# 07-PowerManagement.net
KiCad netlist of a schematic drawn in Altium Designer
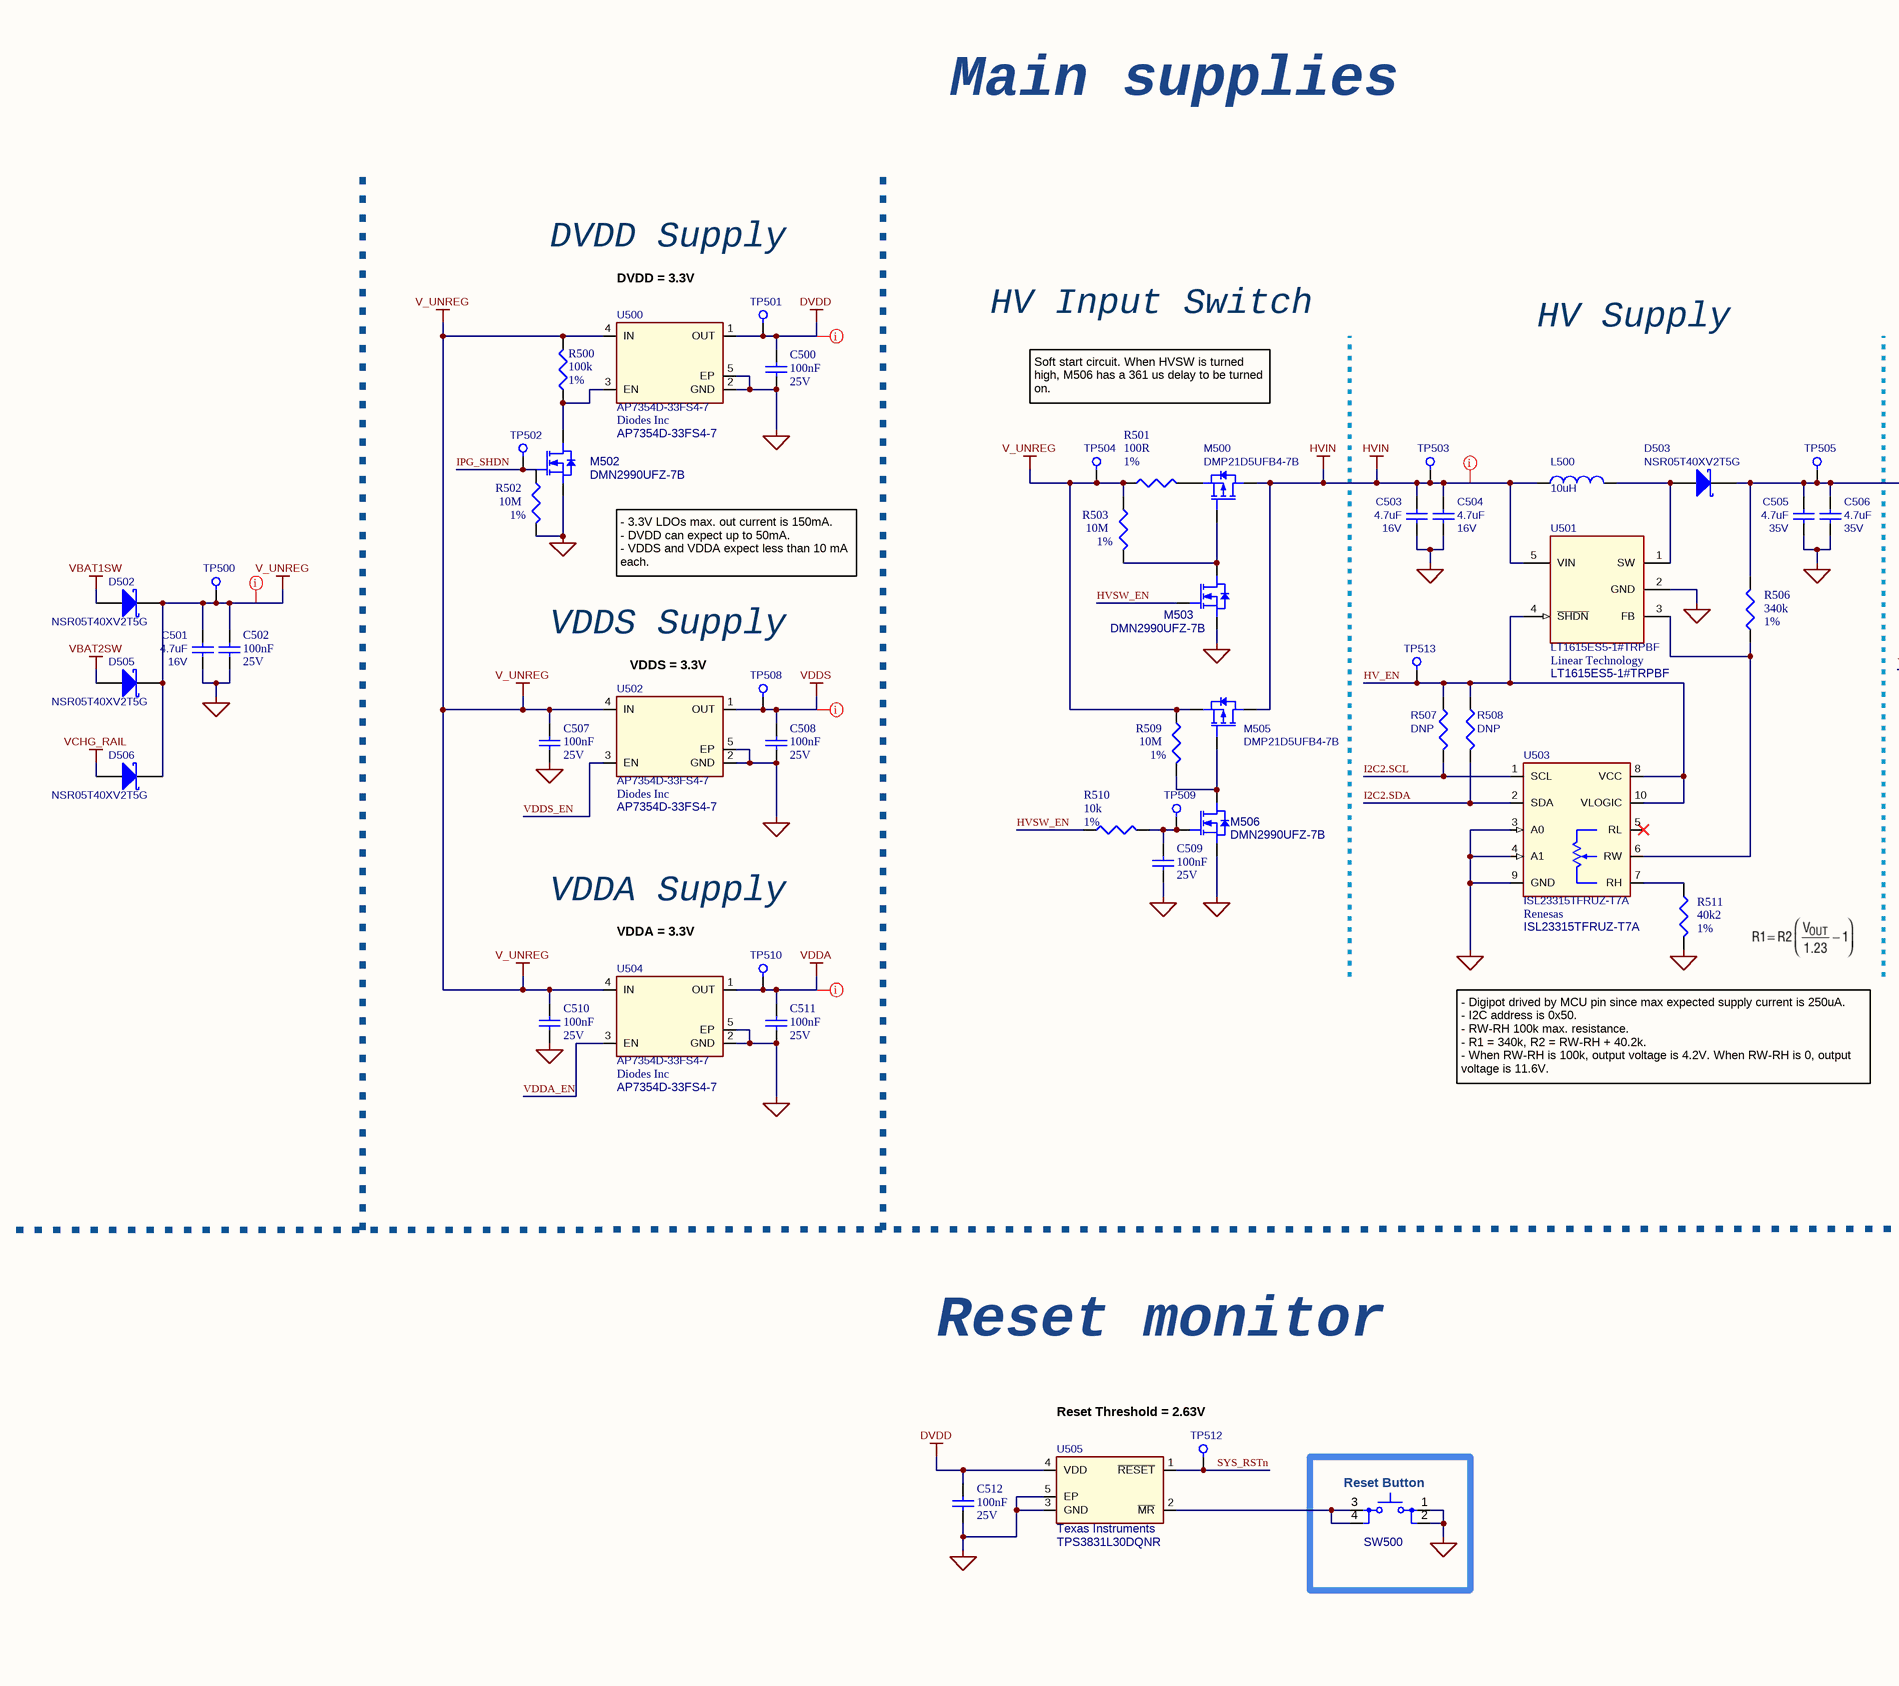
[diagram p0: 07-PowerManagement.SchDoc, left]
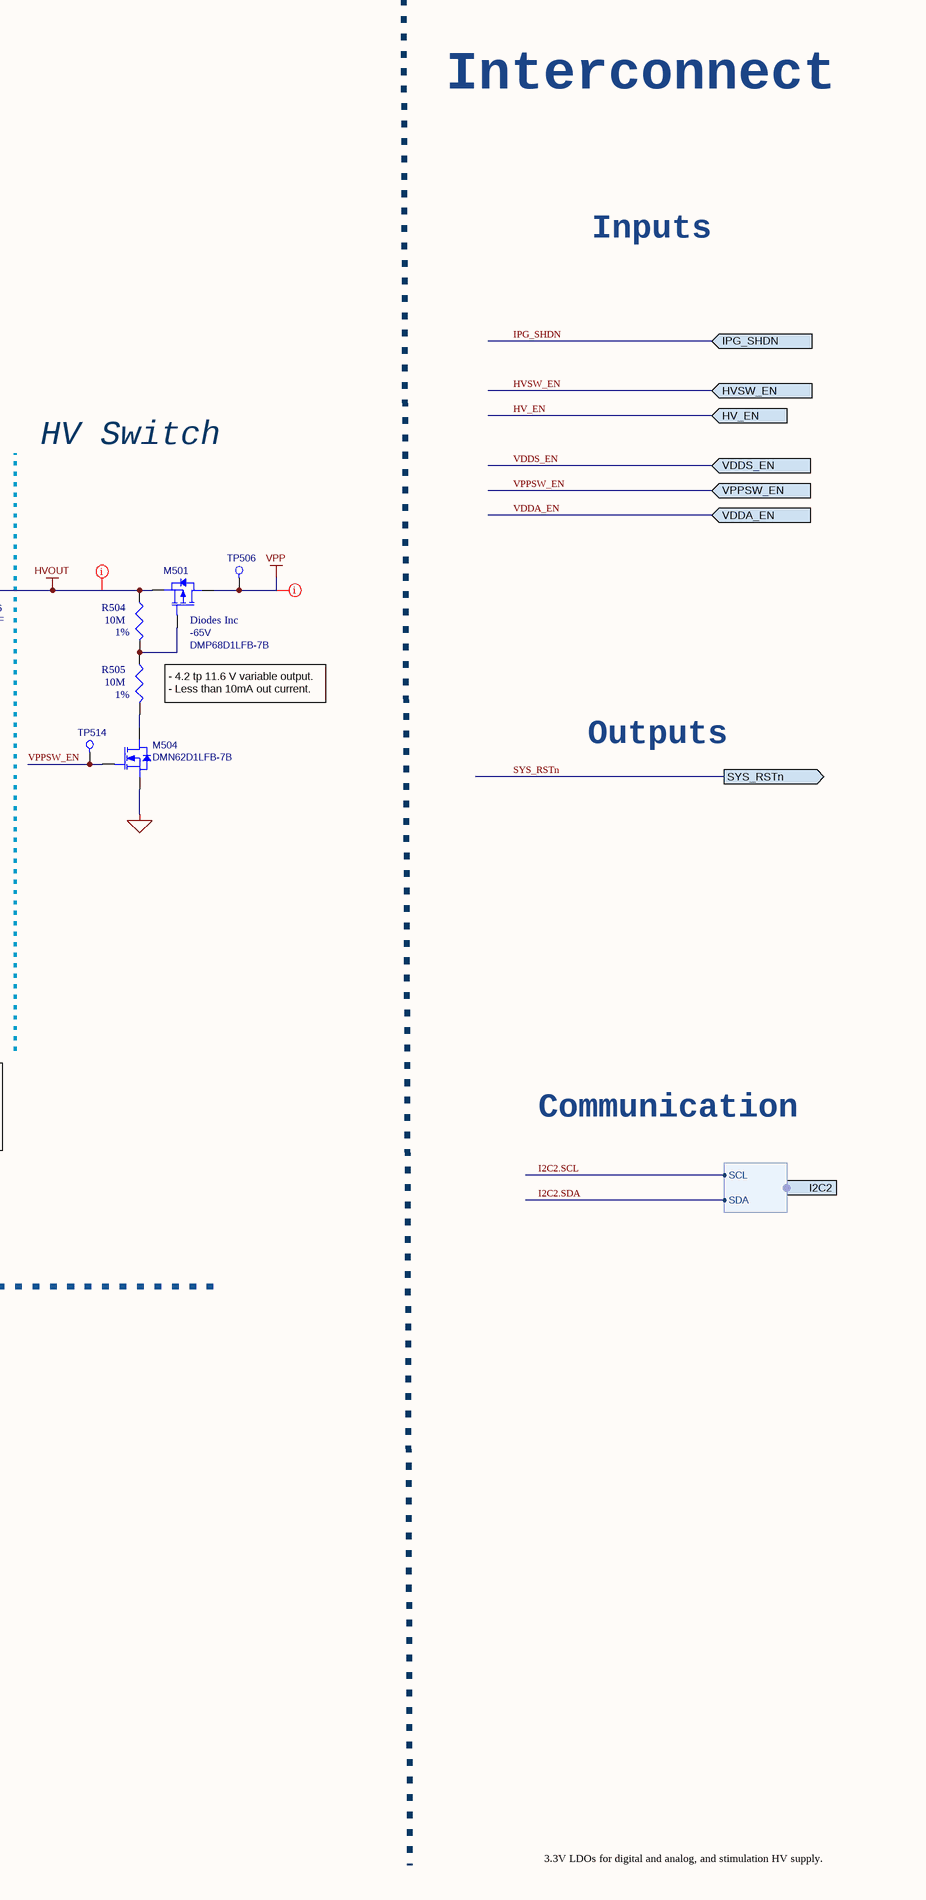
[diagram p1: 07-PowerManagement.SchDoc, right]

(export (version "E")
  (design (tool "Eeschema 10.0.6"))
  (components
    (comp (ref "C500")
      (value "100nF")
      (footprint "C0201_C")
      (fields
        (field (name "MANUFACTURER") "Murata")
        (field (name "MANUFACTURER PART NUMBER") "GRM033R61E104KE14J")
        (field (name "RATED DC VOLTAGE (URDC)") "25V")
      )
      (libsource (lib "MP-LIBRARY") (part "GRM033R61E104KE14J"))
    )
    (comp (ref "C501")
      (value "4.7uF")
      (footprint "CAP0603_REDUCED")
      (description "Capacitor, 4.7uF, X5R, 16V, 10%, 0603, Implant-grade")
      (fields
        (field (name "MANUFACTURER") "Murata")
        (field (name "RATING") "16V")
        (field (name "MANUFACTURER PART NUMBER") "GRM188R61C475KE11")
      )
      (libsource (lib "MP-LIBRARY") (part "GRM188R61C475KE11"))
    )
    (comp (ref "C502")
      (value "100nF")
      (footprint "C0201_C")
      (fields
        (field (name "MANUFACTURER") "Murata")
        (field (name "MANUFACTURER PART NUMBER") "GRM033R61E104KE14J")
        (field (name "RATED DC VOLTAGE (URDC)") "25V")
      )
      (libsource (lib "MP-LIBRARY") (part "GRM033R61E104KE14J"))
    )
    (comp (ref "C503")
      (value "4.7uF")
      (footprint "CAP0603_REDUCED")
      (description "Capacitor, 4.7uF, X5R, 16V, 10%, 0603, Implant-grade")
      (fields
        (field (name "MANUFACTURER") "Murata")
        (field (name "RATING") "16V")
        (field (name "MANUFACTURER PART NUMBER") "GRM188R61C475KE11")
      )
      (libsource (lib "MP-LIBRARY") (part "GRM188R61C475KE11"))
    )
    (comp (ref "C504")
      (value "4.7uF")
      (footprint "CAP0603_REDUCED")
      (description "Capacitor, 4.7uF, X5R, 16V, 10%, 0603, Implant-grade")
      (fields
        (field (name "MANUFACTURER") "Murata")
        (field (name "RATING") "16V")
        (field (name "MANUFACTURER PART NUMBER") "GRM188R61C475KE11")
      )
      (libsource (lib "MP-LIBRARY") (part "GRM188R61C475KE11"))
    )
    (comp (ref "C505")
      (value "4.7uF")
      (footprint "CAP0805_REDUCED")
      (description "Capacitor, 4.7uF, X7S, 35V, 10%, 0805, Implant-grade")
      (fields
        (field (name "MANUFACTURER") "Murata")
        (field (name "RATING") "35V")
        (field (name "MANUFACTURER PART NUMBER") "GCM21BC7YA475KE36L")
      )
      (libsource (lib "MP-LIBRARY") (part "GCM21BC7YA475KE36L"))
    )
    (comp (ref "C506")
      (value "4.7uF")
      (footprint "CAP0805_REDUCED")
      (description "Capacitor, 4.7uF, X7S, 35V, 10%, 0805, Implant-grade")
      (fields
        (field (name "MANUFACTURER") "Murata")
        (field (name "RATING") "35V")
        (field (name "MANUFACTURER PART NUMBER") "GCM21BC7YA475KE36L")
      )
      (libsource (lib "MP-LIBRARY") (part "GCM21BC7YA475KE36L"))
    )
    (comp (ref "C507")
      (value "100nF")
      (footprint "C0201_C")
      (fields
        (field (name "MANUFACTURER") "Murata")
        (field (name "MANUFACTURER PART NUMBER") "GRM033R61E104KE14J")
        (field (name "RATED DC VOLTAGE (URDC)") "25V")
      )
      (libsource (lib "MP-LIBRARY") (part "GRM033R61E104KE14J"))
    )
    (comp (ref "C508")
      (value "100nF")
      (footprint "C0201_C")
      (fields
        (field (name "MANUFACTURER") "Murata")
        (field (name "MANUFACTURER PART NUMBER") "GRM033R61E104KE14J")
        (field (name "RATED DC VOLTAGE (URDC)") "25V")
      )
      (libsource (lib "MP-LIBRARY") (part "GRM033R61E104KE14J"))
    )
    (comp (ref "C509")
      (value "100nF")
      (footprint "C0201_C")
      (fields
        (field (name "MANUFACTURER") "Murata")
        (field (name "MANUFACTURER PART NUMBER") "GRM033R61E104KE14J")
        (field (name "RATED DC VOLTAGE (URDC)") "25V")
      )
      (libsource (lib "MP-LIBRARY") (part "GRM033R61E104KE14J"))
    )
    (comp (ref "C510")
      (value "100nF")
      (footprint "C0201_C")
      (fields
        (field (name "MANUFACTURER") "Murata")
        (field (name "MANUFACTURER PART NUMBER") "GRM033R61E104KE14J")
        (field (name "RATED DC VOLTAGE (URDC)") "25V")
      )
      (libsource (lib "MP-LIBRARY") (part "GRM033R61E104KE14J"))
    )
    (comp (ref "C511")
      (value "100nF")
      (footprint "C0201_C")
      (fields
        (field (name "MANUFACTURER") "Murata")
        (field (name "MANUFACTURER PART NUMBER") "GRM033R61E104KE14J")
        (field (name "RATED DC VOLTAGE (URDC)") "25V")
      )
      (libsource (lib "MP-LIBRARY") (part "GRM033R61E104KE14J"))
    )
    (comp (ref "C512")
      (value "100nF")
      (footprint "C0201_C")
      (fields
        (field (name "MANUFACTURER") "Murata")
        (field (name "MANUFACTURER PART NUMBER") "GRM033R61E104KE14J")
        (field (name "RATED DC VOLTAGE (URDC)") "25V")
      )
      (libsource (lib "MP-LIBRARY") (part "GRM033R61E104KE14J"))
    )
    (comp (ref "D502")
      (value "NSR05T40XV2T5G")
      (footprint "STM_SOD-523_R")
      (description "Schottky, 40V, 500mA, 530mV, SOD-523")
      (fields (field (name "MANUFACTURER") "ON Semiconductor"))
      (libsource (lib "MP-LIBRARY") (part "NSR05T40XV2T5G"))
    )
    (comp (ref "D503")
      (value "NSR05T40XV2T5G")
      (footprint "STM_SOD-523_R")
      (description "Schottky, 40V, 500mA, 530mV, SOD-523")
      (fields (field (name "MANUFACTURER") "ON Semiconductor"))
      (libsource (lib "MP-LIBRARY") (part "NSR05T40XV2T5G"))
    )
    (comp (ref "D505")
      (value "NSR05T40XV2T5G")
      (footprint "STM_SOD-523_R")
      (description "Schottky, 40V, 500mA, 530mV, SOD-523")
      (fields (field (name "MANUFACTURER") "ON Semiconductor"))
      (libsource (lib "MP-LIBRARY") (part "NSR05T40XV2T5G"))
    )
    (comp (ref "D506")
      (value "NSR05T40XV2T5G")
      (footprint "STM_SOD-523_R")
      (description "Schottky, 40V, 500mA, 530mV, SOD-523")
      (fields (field (name "MANUFACTURER") "ON Semiconductor"))
      (libsource (lib "MP-LIBRARY") (part "NSR05T40XV2T5G"))
    )
    (comp (ref "L500")
      (value "10uH")
      (footprint "WURTH_74438323100_REDUCED")
      (description "Inductor, 10uH, 600mA, 20%, 1008")
      (fields (field (name "MANUFACTURER") "Wurth") (field (name "MANUFACTURER PART NUMBER") "74438323100"))
      (libsource (lib "MP-LIBRARY") (part "74438323100"))
    )
    (comp (ref "M500")
      (value "DMP21D5UFB4-7B")
      (footprint "DIODESINC_X2-DFN1006-3_REDUCED")
      (description "MOSFET, P-chan, -20V, -400mA, X2-DFN1006-3")
      (fields (field (name "MANUFACTURER") "Diodes Inc"))
      (libsource (lib "MP-LIBRARY") (part "DMP21D5UFB4-7B"))
    )
    (comp (ref "M501")
      (value "DMP68D1LFB-7B")
      (footprint "DIODESINC_X1-DFN1006-3")
      (description "MOSFET, P-chan, -65V, -290mA, DFN1006")
      (fields
        (field (name "MANUFACTURER") "Diodes Inc")
        (field (name "RATING") "-65V")
        (field (name "MANUFACTURER PART NUMBER") "DMP68D1LFB")
      )
      (libsource (lib "MP-LIBRARY") (part "DMP68D1LFB-7B"))
    )
    (comp (ref "M502")
      (value "DMN2990UFZ-7B")
      (footprint "DIODESINC_X2-DFN0606-3")
      (description "MOSFET, N-Chan, 20V, 170mA, DFN0606")
      (fields (field (name "MANUFACTURER") "Diodes Inc"))
      (libsource (lib "MP-LIBRARY") (part "DMN2990UFZ-7B"))
    )
    (comp (ref "M503")
      (value "DMN2990UFZ-7B")
      (footprint "DIODESINC_X2-DFN0606-3")
      (description "MOSFET, N-Chan, 20V, 170mA, DFN0606")
      (fields (field (name "MANUFACTURER") "Diodes Inc"))
      (libsource (lib "MP-LIBRARY") (part "DMN2990UFZ-7B"))
    )
    (comp (ref "M504")
      (value "DMN62D1LFB-7B")
      (footprint "DIODESINC_X1-DFN1006-3")
      (description "MOSFET, N-Chan, 60V, 320mA, DFN1006")
      (fields (field (name "MANUFACTURER") "Diodes Inc"))
      (libsource (lib "MP-LIBRARY") (part "DMN62D1LFB-7B"))
    )
    (comp (ref "M505")
      (value "DMP21D5UFB4-7B")
      (footprint "DIODESINC_X2-DFN1006-3_REDUCED")
      (description "MOSFET, P-chan, -20V, -400mA, X2-DFN1006-3")
      (fields (field (name "MANUFACTURER") "Diodes Inc"))
      (libsource (lib "MP-LIBRARY") (part "DMP21D5UFB4-7B"))
    )
    (comp (ref "M506")
      (value "DMN2990UFZ-7B")
      (footprint "DIODESINC_X2-DFN0606-3")
      (description "MOSFET, N-Chan, 20V, 170mA, DFN0606")
      (fields (field (name "MANUFACTURER") "Diodes Inc"))
      (libsource (lib "MP-LIBRARY") (part "DMN2990UFZ-7B"))
    )
    (comp (ref "R500")
      (value "100k")
      (footprint "R0201_C")
      (fields
        (field (name "MANUFACTURER") "Vishay")
        (field (name "MANUFACTURER PART NUMBER") "CRCW0201100KFNED")
        (field (name "TOLERANCE") "1%")
        (field (name "POWER") "50mW")
      )
      (libsource (lib "MP-LIBRARY") (part "CRCW0201100KFNED"))
    )
    (comp (ref "R501")
      (value "100R")
      (footprint "R0201_C")
      (fields
        (field (name "MANUFACTURER") "Vishay")
        (field (name "MANUFACTURER PART NUMBER") "CRCW0201100RFNED")
        (field (name "TOLERANCE") "1%")
        (field (name "POWER") "50mW")
      )
      (libsource (lib "MP-LIBRARY") (part "CRCW0201100RFNED"))
    )
    (comp (ref "R502")
      (value "10M")
      (footprint "R0201_C")
      (fields
        (field (name "MANUFACTURER") "Vishay Draloric")
        (field (name "MANUFACTURER PART NUMBER") "CRCW020110M0FNED")
        (field (name "TOLERANCE") "1%")
        (field (name "POWER") "50mW")
      )
      (libsource (lib "MP-LIBRARY") (part "CRCW020110M0FNED"))
    )
    (comp (ref "R503")
      (value "10M")
      (footprint "R0201_C")
      (fields
        (field (name "MANUFACTURER") "Vishay Draloric")
        (field (name "MANUFACTURER PART NUMBER") "CRCW020110M0FNED")
        (field (name "TOLERANCE") "1%")
        (field (name "POWER") "50mW")
      )
      (libsource (lib "MP-LIBRARY") (part "CRCW020110M0FNED"))
    )
    (comp (ref "R504")
      (value "10M")
      (footprint "R0201_C")
      (fields
        (field (name "MANUFACTURER") "Vishay Draloric")
        (field (name "MANUFACTURER PART NUMBER") "CRCW020110M0FNED")
        (field (name "TOLERANCE") "1%")
        (field (name "POWER") "50mW")
      )
      (libsource (lib "MP-LIBRARY") (part "CRCW020110M0FNED"))
    )
    (comp (ref "R505")
      (value "10M")
      (footprint "R0201_C")
      (fields
        (field (name "MANUFACTURER") "Vishay Draloric")
        (field (name "MANUFACTURER PART NUMBER") "CRCW020110M0FNED")
        (field (name "TOLERANCE") "1%")
        (field (name "POWER") "50mW")
      )
      (libsource (lib "MP-LIBRARY") (part "CRCW020110M0FNED"))
    )
    (comp (ref "R506")
      (value "340k")
      (footprint "R0201_C")
      (fields
        (field (name "MANUFACTURER") "Vishay")
        (field (name "MANUFACTURER PART NUMBER") "CRCW0201340KFKED")
        (field (name "TOLERANCE") "1%")
        (field (name "POWER") "50mW")
      )
      (libsource (lib "MP-LIBRARY") (part "CRCW0201340KFKED"))
    )
    (comp (ref "R507")
      (value "DNP")
      (footprint "RES0402_REDUCED")
      (description "Resistor, DNP, 0402")
      (libsource (lib "MP-LIBRARY") (part "RES_DNP_0402"))
    )
    (comp (ref "R508")
      (value "DNP")
      (footprint "RES0402_REDUCED")
      (description "Resistor, DNP, 0402")
      (libsource (lib "MP-LIBRARY") (part "RES_DNP_0402"))
    )
    (comp (ref "R509")
      (value "10M")
      (footprint "R0201_C")
      (fields
        (field (name "MANUFACTURER") "Vishay Draloric")
        (field (name "MANUFACTURER PART NUMBER") "CRCW020110M0FNED")
        (field (name "TOLERANCE") "1%")
        (field (name "POWER") "50mW")
      )
      (libsource (lib "MP-LIBRARY") (part "CRCW020110M0FNED"))
    )
    (comp (ref "R510")
      (value "10k")
      (footprint "R0201_C")
      (fields
        (field (name "MANUFACTURER") "Vishay")
        (field (name "MANUFACTURER PART NUMBER") "CRCW020110K0FNED")
        (field (name "TOLERANCE") "1%")
        (field (name "POWER") "50mW")
      )
      (libsource (lib "MP-LIBRARY") (part "CRCW020110K0FNED"))
    )
    (comp (ref "R511")
      (value "40k2")
      (footprint "R0201_C")
      (fields
        (field (name "MANUFACTURER") "Vishay")
        (field (name "MANUFACTURER PART NUMBER") "CRCW020140K2FNED")
        (field (name "TOLERANCE") "1%")
        (field (name "POWER") "50mW")
      )
      (libsource (lib "MP-LIBRARY") (part "CRCW020140K2FNED"))
    )
    (comp (ref "SW500")
      (value "PB")
      (footprint "CK_PTS647")
      (description "Pushbutton, NO-MOM, 12V, 0.05A, SMT")
      (fields
        (field (name "MANUFACTURER") "C&K")
        (field (name "MANUFACTURER PART NUMBER") "PTS647SN50SMTR2LFS")
      )
      (libsource (lib "MP-LIBRARY") (part "PTS647SN50SMTR2LFS"))
    )
    (comp (ref "TP500")
      (value "Test Point")
      (footprint "testpad_0.9mm")
      (description "Test pad, 0.90mm circular pad")
      (libsource (lib "MP-LIBRARY") (part "Test Point"))
    )
    (comp (ref "TP501")
      (value "Test Point")
      (footprint "testpad_0.9mm")
      (description "Test pad, 0.90mm circular pad")
      (libsource (lib "MP-LIBRARY") (part "Test Point"))
    )
    (comp (ref "TP502")
      (value "Test Point")
      (footprint "testpad_0.9mm")
      (description "Test pad, 0.90mm circular pad")
      (libsource (lib "MP-LIBRARY") (part "Test Point"))
    )
    (comp (ref "TP503")
      (value "Test Point")
      (footprint "testpad_0.9mm")
      (description "Test pad, 0.90mm circular pad")
      (libsource (lib "MP-LIBRARY") (part "Test Point"))
    )
    (comp (ref "TP504")
      (value "Test Point")
      (footprint "testpad_0.9mm")
      (description "Test pad, 0.90mm circular pad")
      (libsource (lib "MP-LIBRARY") (part "Test Point"))
    )
    (comp (ref "TP505")
      (value "Test Point")
      (footprint "testpad_0.9mm")
      (description "Test pad, 0.90mm circular pad")
      (libsource (lib "MP-LIBRARY") (part "Test Point"))
    )
    (comp (ref "TP506")
      (value "Test Point")
      (footprint "testpad_0.9mm")
      (description "Test pad, 0.90mm circular pad")
      (libsource (lib "MP-LIBRARY") (part "Test Point"))
    )
    (comp (ref "TP508")
      (value "Test Point")
      (footprint "testpad_0.9mm")
      (description "Test pad, 0.90mm circular pad")
      (libsource (lib "MP-LIBRARY") (part "Test Point"))
    )
    (comp (ref "TP509")
      (value "Test Point")
      (footprint "testpad_0.9mm")
      (description "Test pad, 0.90mm circular pad")
      (libsource (lib "MP-LIBRARY") (part "Test Point"))
    )
    (comp (ref "TP510")
      (value "Test Point")
      (footprint "testpad_0.9mm")
      (description "Test pad, 0.90mm circular pad")
      (libsource (lib "MP-LIBRARY") (part "Test Point"))
    )
    (comp (ref "TP512")
      (value "Test Point")
      (footprint "testpad_0.9mm")
      (description "Test pad, 0.90mm circular pad")
      (libsource (lib "MP-LIBRARY") (part "Test Point"))
    )
    (comp (ref "TP513")
      (value "Test Point")
      (footprint "testpad_0.9mm")
      (description "Test pad, 0.90mm circular pad")
      (libsource (lib "MP-LIBRARY") (part "Test Point"))
    )
    (comp (ref "TP514")
      (value "Test Point")
      (footprint "testpad_0.9mm")
      (description "Test pad, 0.90mm circular pad")
      (libsource (lib "MP-LIBRARY") (part "Test Point"))
    )
    (comp (ref "U500")
      (value "AP7354D-33FS4-7")
      (footprint "X2-DFN1010-4 (Type B)")
      (description "LDO Regulator, 3.3V, Shutdown, DFN1010-4")
      (fields (field (name "MANUFACTURER") "Diodes Inc") (field (name "ALTIUM_VALUE") "AP7354D-33FS4-7"))
      (libsource (lib "MP-LIBRARY") (part "AP7354D-33FS4-7"))
    )
    (comp (ref "U501")
      (value "LT1615ES5-1#TRPBF")
      (footprint "LT_S5_L")
      (description "Boost, SEPIC Switching Regulator IC Positive Adjustable 1.23V 1 Output 75mA (Switch) SOT-23-5")
      (fields
        (field (name "MANUFACTURER") "Linear Technology")
        (field (name "ALTIUM_VALUE") "LT1615ES5-1#TRPBF")
      )
      (libsource (lib "MP-LIBRARY") (part "LT1615ES5-1#TRPBF"))
    )
    (comp (ref "U502")
      (value "AP7354D-33FS4-7")
      (footprint "X2-DFN1010-4 (Type B)")
      (description "LDO Regulator, 3.3V, Shutdown, DFN1010-4")
      (fields (field (name "MANUFACTURER") "Diodes Inc") (field (name "ALTIUM_VALUE") "AP7354D-33FS4-7"))
      (libsource (lib "MP-LIBRARY") (part "AP7354D-33FS4-7"))
    )
    (comp (ref "U503")
      (value "ISL23315TFRUZ-T7A")
      (footprint "RENESAS_L10.2.1X1.6A_UTQFN10")
      (description "Digital potentiometer, 256 taps, 100k, I2C, QFN-10")
      (fields (field (name "MANUFACTURER") "Renesas") (field (name "ALTIUM_VALUE") "ISL23315TFRUZ-T7A"))
      (libsource (lib "MP-LIBRARY") (part "ISL23315TFRUZ-T7A"))
    )
    (comp (ref "U504")
      (value "AP7354D-33FS4-7")
      (footprint "X2-DFN1010-4 (Type B)")
      (description "LDO Regulator, 3.3V, Shutdown, DFN1010-4")
      (fields (field (name "MANUFACTURER") "Diodes Inc") (field (name "ALTIUM_VALUE") "AP7354D-33FS4-7"))
      (libsource (lib "MP-LIBRARY") (part "AP7354D-33FS4-7"))
    )
    (comp (ref "U505")
      (value "TPS3831L30DQNR")
      (footprint "TI_X2SON_DQN0004A")
      (description "Reset Monitor, 2.63V, Active low, X2SON")
      (fields (field (name "MANUFACTURER") "Texas Instruments"))
      (libsource (lib "MP-LIBRARY") (part "TPS3831L30DQNR"))
    )
  )
  (nets
    (net (code "2") (name "/HVSW_EN") (class "Default")
      (node (ref "M503") (pin "1") (pinfunction "G_1") (pintype "passive"))
      (node (ref "R510") (pin "1") (pinfunction "1_1") (pintype "passive"))
    )
    (net (code "3") (name "/HV_EN") (class "Default")
      (node (ref "R507") (pin "1") (pinfunction "1_1") (pintype "passive"))
      (node (ref "R508") (pin "1") (pinfunction "1_1") (pintype "passive"))
      (node (ref "TP513") (pin "1") (pinfunction "1_1") (pintype "passive"))
      (node (ref "U501") (pin "4") (pinfunction "~{SHDN}_4") (pintype "input"))
      (node (ref "U503") (pin "10") (pinfunction "VLOGIC_10") (pintype "passive"))
      (node (ref "U503") (pin "8") (pinfunction "VCC_8") (pintype "passive"))
    )
    (net (code "4") (name "/I2C2.SCL") (class "Default")
      (node (ref "R507") (pin "2") (pinfunction "2_2") (pintype "passive"))
      (node (ref "U503") (pin "1") (pinfunction "SCL_1") (pintype "passive"))
    )
    (net (code "5") (name "/I2C2.SDA") (class "Default")
      (node (ref "R508") (pin "2") (pinfunction "2_2") (pintype "passive"))
      (node (ref "U503") (pin "2") (pinfunction "SDA_2") (pintype "passive"))
    )
    (net (code "6") (name "/IPG_SHDN") (class "Default")
      (node (ref "M502") (pin "1") (pinfunction "G_1") (pintype "passive"))
      (node (ref "R502") (pin "1") (pinfunction "1_1") (pintype "passive"))
      (node (ref "TP502") (pin "1") (pinfunction "1_1") (pintype "passive"))
    )
    (net (code "7") (name "/SYS_RSTn") (class "Default")
      (node (ref "TP512") (pin "1") (pinfunction "1_1") (pintype "passive"))
      (node (ref "U505") (pin "1") (pinfunction "~{RESET}_1") (pintype "passive"))
    )
    (net (code "8") (name "/VDDA_EN") (class "Default")
      (node (ref "U504") (pin "3") (pinfunction "EN_3") (pintype "passive"))
    )
    (net (code "9") (name "/VDDS_EN") (class "Default")
      (node (ref "U502") (pin "3") (pinfunction "EN_3") (pintype "passive"))
    )
    (net (code "10") (name "/VPPSW_EN") (class "Default")
      (node (ref "M504") (pin "1") (pinfunction "G_1") (pintype "passive"))
      (node (ref "TP514") (pin "1") (pinfunction "1_1") (pintype "passive"))
    )
    (net (code "12") (name "DVDD") (class "Default")
      (node (ref "C500") (pin "2") (pinfunction "2_2") (pintype "passive"))
      (node (ref "C512") (pin "2") (pinfunction "2_2") (pintype "passive"))
      (node (ref "TP501") (pin "1") (pinfunction "1_1") (pintype "passive"))
      (node (ref "U500") (pin "1") (pinfunction "OUT_1") (pintype "passive"))
      (node (ref "U505") (pin "4") (pinfunction "VDD_4") (pintype "passive"))
    )
    (net (code "13") (name "GND") (class "Default")
      (node (ref "C500") (pin "1") (pinfunction "1_1") (pintype "passive"))
      (node (ref "C501") (pin "2") (pinfunction "2_2") (pintype "passive"))
      (node (ref "C502") (pin "1") (pinfunction "1_1") (pintype "passive"))
      (node (ref "C503") (pin "2") (pinfunction "2_2") (pintype "passive"))
      (node (ref "C504") (pin "2") (pinfunction "2_2") (pintype "passive"))
      (node (ref "C505") (pin "2") (pinfunction "2_2") (pintype "passive"))
      (node (ref "C506") (pin "2") (pinfunction "2_2") (pintype "passive"))
      (node (ref "C507") (pin "1") (pinfunction "1_1") (pintype "passive"))
      (node (ref "C508") (pin "1") (pinfunction "1_1") (pintype "passive"))
      (node (ref "C509") (pin "1") (pinfunction "1_1") (pintype "passive"))
      (node (ref "C510") (pin "1") (pinfunction "1_1") (pintype "passive"))
      (node (ref "C511") (pin "1") (pinfunction "1_1") (pintype "passive"))
      (node (ref "C512") (pin "1") (pinfunction "1_1") (pintype "passive"))
      (node (ref "M502") (pin "2") (pinfunction "S_2") (pintype "passive"))
      (node (ref "M503") (pin "2") (pinfunction "S_2") (pintype "passive"))
      (node (ref "M504") (pin "2") (pinfunction "S_2") (pintype "passive"))
      (node (ref "M506") (pin "2") (pinfunction "S_2") (pintype "passive"))
      (node (ref "R502") (pin "2") (pinfunction "2_2") (pintype "passive"))
      (node (ref "R511") (pin "2") (pinfunction "2_2") (pintype "passive"))
      (node (ref "SW500") (pin "1") (pinfunction "1_1") (pintype "passive"))
      (node (ref "SW500") (pin "2") (pinfunction "2_2") (pintype "passive"))
      (node (ref "U500") (pin "2") (pinfunction "GND_2") (pintype "power_in"))
      (node (ref "U500") (pin "5") (pinfunction "EP_5") (pintype "passive"))
      (node (ref "U501") (pin "2") (pinfunction "GND_2") (pintype "power_in"))
      (node (ref "U502") (pin "2") (pinfunction "GND_2") (pintype "power_in"))
      (node (ref "U502") (pin "5") (pinfunction "EP_5") (pintype "passive"))
      (node (ref "U503") (pin "3") (pinfunction "A0_3") (pintype "input"))
      (node (ref "U503") (pin "4") (pinfunction "A1_4") (pintype "input"))
      (node (ref "U503") (pin "9") (pinfunction "GND_9") (pintype "power_in"))
      (node (ref "U504") (pin "2") (pinfunction "GND_2") (pintype "power_in"))
      (node (ref "U504") (pin "5") (pinfunction "EP_5") (pintype "passive"))
      (node (ref "U505") (pin "3") (pinfunction "GND_3") (pintype "passive"))
      (node (ref "U505") (pin "5") (pinfunction "EP_5") (pintype "passive"))
    )
    (net (code "14") (name "HVIN") (class "Default")
      (node (ref "C503") (pin "1") (pinfunction "1_1") (pintype "passive"))
      (node (ref "C504") (pin "1") (pinfunction "1_1") (pintype "passive"))
      (node (ref "L500") (pin "1") (pinfunction "1_1") (pintype "passive"))
      (node (ref "M500") (pin "3") (pinfunction "D_3") (pintype "passive"))
      (node (ref "M505") (pin "3") (pinfunction "D_3") (pintype "passive"))
      (node (ref "TP503") (pin "1") (pinfunction "1_1") (pintype "passive"))
      (node (ref "U501") (pin "5") (pinfunction "VIN_5") (pintype "power_in"))
    )
    (net (code "15") (name "HVOUT") (class "Default")
      (node (ref "C505") (pin "1") (pinfunction "1_1") (pintype "passive"))
      (node (ref "C506") (pin "1") (pinfunction "1_1") (pintype "passive"))
      (node (ref "D503") (pin "1") (pinfunction "K_1") (pintype "passive"))
      (node (ref "M501") (pin "2") (pinfunction "S_2") (pintype "passive"))
      (node (ref "R504") (pin "1") (pinfunction "1_1") (pintype "passive"))
      (node (ref "R506") (pin "2") (pinfunction "2_2") (pintype "passive"))
      (node (ref "TP505") (pin "1") (pinfunction "1_1") (pintype "passive"))
    )
    (net (code "16") (name "Net-(D503-A)") (class "Default")
      (node (ref "D503") (pin "2") (pinfunction "A_2") (pintype "passive"))
      (node (ref "L500") (pin "2") (pinfunction "2_2") (pintype "passive"))
      (node (ref "U501") (pin "1") (pinfunction "SW_1") (pintype "passive"))
    )
    (net (code "17") (name "Net-(M500-G)") (class "Default")
      (node (ref "M500") (pin "1") (pinfunction "G_1") (pintype "passive"))
      (node (ref "M503") (pin "3") (pinfunction "D_3") (pintype "passive"))
      (node (ref "R503") (pin "2") (pinfunction "2_2") (pintype "passive"))
    )
    (net (code "18") (name "Net-(M500-S)") (class "Default")
      (node (ref "M500") (pin "2") (pinfunction "S_2") (pintype "passive"))
      (node (ref "R501") (pin "2") (pinfunction "2_2") (pintype "passive"))
    )
    (net (code "19") (name "Net-(M501-G)") (class "Default")
      (node (ref "M501") (pin "1") (pinfunction "G_1") (pintype "passive"))
      (node (ref "R504") (pin "2") (pinfunction "2_2") (pintype "passive"))
      (node (ref "R505") (pin "1") (pinfunction "1_1") (pintype "passive"))
    )
    (net (code "20") (name "Net-(M502-D)") (class "Default")
      (node (ref "M502") (pin "3") (pinfunction "D_3") (pintype "passive"))
      (node (ref "R500") (pin "1") (pinfunction "1_1") (pintype "passive"))
      (node (ref "U500") (pin "3") (pinfunction "EN_3") (pintype "passive"))
    )
    (net (code "21") (name "Net-(M504-D)") (class "Default")
      (node (ref "M504") (pin "3") (pinfunction "D_3") (pintype "passive"))
      (node (ref "R505") (pin "2") (pinfunction "2_2") (pintype "passive"))
    )
    (net (code "22") (name "Net-(M505-G)") (class "Default")
      (node (ref "M505") (pin "1") (pinfunction "G_1") (pintype "passive"))
      (node (ref "M506") (pin "3") (pinfunction "D_3") (pintype "passive"))
      (node (ref "R509") (pin "2") (pinfunction "2_2") (pintype "passive"))
    )
    (net (code "23") (name "Net-(M506-G)") (class "Default")
      (node (ref "C509") (pin "2") (pinfunction "2_2") (pintype "passive"))
      (node (ref "M506") (pin "1") (pinfunction "G_1") (pintype "passive"))
      (node (ref "R510") (pin "2") (pinfunction "2_2") (pintype "passive"))
      (node (ref "TP509") (pin "1") (pinfunction "1_1") (pintype "passive"))
    )
    (net (code "24") (name "Net-(U501-FB)") (class "Default")
      (node (ref "R506") (pin "1") (pinfunction "1_1") (pintype "passive"))
      (node (ref "U501") (pin "3") (pinfunction "FB_3") (pintype "passive"))
      (node (ref "U503") (pin "6") (pinfunction "RW_6") (pintype "passive"))
    )
    (net (code "25") (name "Net-(U503-RH)") (class "Default")
      (node (ref "R511") (pin "1") (pinfunction "1_1") (pintype "passive"))
      (node (ref "U503") (pin "7") (pinfunction "RH_7") (pintype "passive"))
    )
    (net (code "26") (name "Net-(U505-~{MR})") (class "Default")
      (node (ref "SW500") (pin "3") (pinfunction "3_3") (pintype "passive"))
      (node (ref "SW500") (pin "4") (pinfunction "4_4") (pintype "passive"))
      (node (ref "U505") (pin "2") (pinfunction "~{MR}_2") (pintype "passive"))
    )
    (net (code "27") (name "VBAT1SW") (class "Default")
      (node (ref "D502") (pin "2") (pinfunction "A_2") (pintype "passive"))
    )
    (net (code "28") (name "VBAT2SW") (class "Default")
      (node (ref "D505") (pin "2") (pinfunction "A_2") (pintype "passive"))
    )
    (net (code "29") (name "VCHG_RAIL") (class "Default")
      (node (ref "D506") (pin "2") (pinfunction "A_2") (pintype "passive"))
    )
    (net (code "30") (name "VDDA") (class "Default")
      (node (ref "C511") (pin "2") (pinfunction "2_2") (pintype "passive"))
      (node (ref "TP510") (pin "1") (pinfunction "1_1") (pintype "passive"))
      (node (ref "U504") (pin "1") (pinfunction "OUT_1") (pintype "passive"))
    )
    (net (code "31") (name "VDDS") (class "Default")
      (node (ref "C508") (pin "2") (pinfunction "2_2") (pintype "passive"))
      (node (ref "TP508") (pin "1") (pinfunction "1_1") (pintype "passive"))
      (node (ref "U502") (pin "1") (pinfunction "OUT_1") (pintype "passive"))
    )
    (net (code "32") (name "VPP") (class "Default")
      (node (ref "M501") (pin "3") (pinfunction "D_3") (pintype "passive"))
      (node (ref "TP506") (pin "1") (pinfunction "1_1") (pintype "passive"))
    )
    (net (code "33") (name "V_UNREG") (class "Default")
      (node (ref "C501") (pin "1") (pinfunction "1_1") (pintype "passive"))
      (node (ref "C502") (pin "2") (pinfunction "2_2") (pintype "passive"))
      (node (ref "C507") (pin "2") (pinfunction "2_2") (pintype "passive"))
      (node (ref "C510") (pin "2") (pinfunction "2_2") (pintype "passive"))
      (node (ref "D502") (pin "1") (pinfunction "K_1") (pintype "passive"))
      (node (ref "D505") (pin "1") (pinfunction "K_1") (pintype "passive"))
      (node (ref "D506") (pin "1") (pinfunction "K_1") (pintype "passive"))
      (node (ref "M505") (pin "2") (pinfunction "S_2") (pintype "passive"))
      (node (ref "R500") (pin "2") (pinfunction "2_2") (pintype "passive"))
      (node (ref "R501") (pin "1") (pinfunction "1_1") (pintype "passive"))
      (node (ref "R503") (pin "1") (pinfunction "1_1") (pintype "passive"))
      (node (ref "R509") (pin "1") (pinfunction "1_1") (pintype "passive"))
      (node (ref "TP500") (pin "1") (pinfunction "1_1") (pintype "passive"))
      (node (ref "TP504") (pin "1") (pinfunction "1_1") (pintype "passive"))
      (node (ref "U500") (pin "4") (pinfunction "IN_4") (pintype "passive"))
      (node (ref "U502") (pin "4") (pinfunction "IN_4") (pintype "passive"))
      (node (ref "U504") (pin "4") (pinfunction "IN_4") (pintype "passive"))
    )
    (net (code "34") (name "unconnected-(U503-RL-Pad5)") (class "Default")
      (node (ref "U503") (pin "5") (pinfunction "RL_5") (pintype "passive+no_connect"))
    )
  )
)
